# lab4.net
KiCad netlist of a schematic drawn in EAGLE
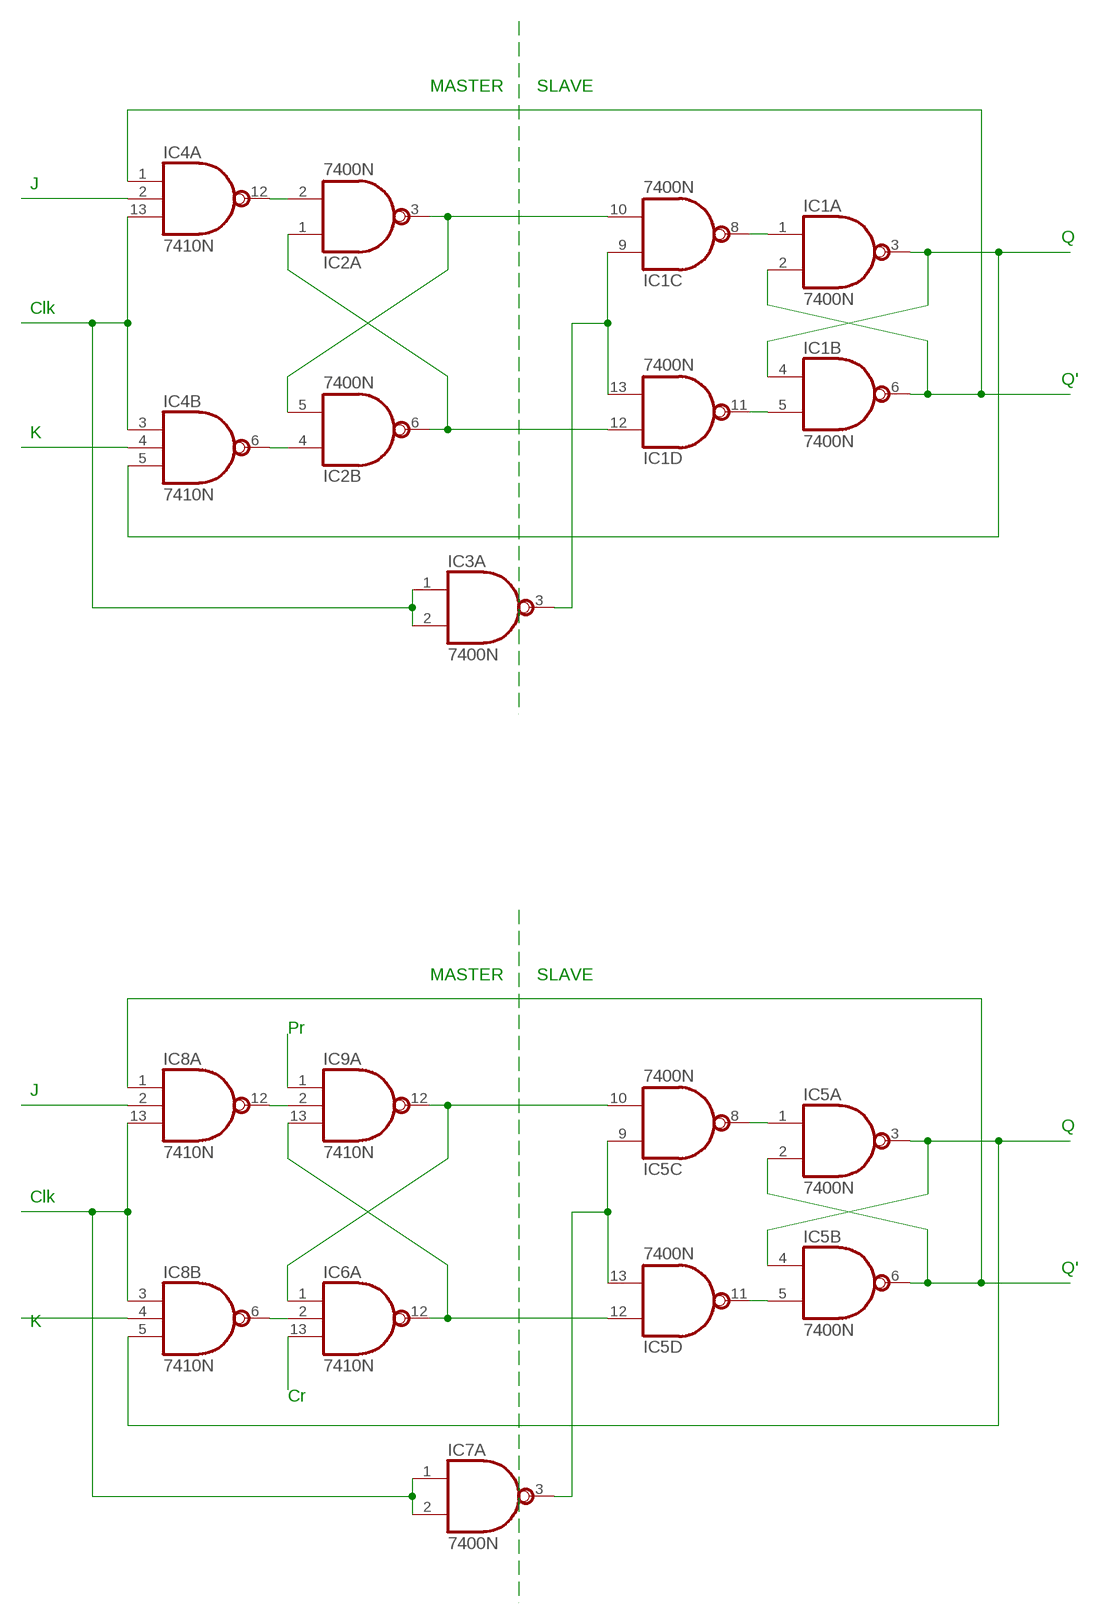
[diagram p0: schematic, sheet 1]

(export (version "E")
  (design (tool "Eeschema 10.0.6"))
  (components
    (comp (ref "IC1")
      (value "7400N")
      (footprint "eagle-import:DIL14")
      (libsource (lib "eagle-import") (part "7400N"))
    )
    (comp (ref "IC2")
      (value "7400N")
      (footprint "eagle-import:DIL14")
      (libsource (lib "eagle-import") (part "7400N"))
    )
    (comp (ref "IC3")
      (value "7400N")
      (footprint "eagle-import:DIL14")
      (libsource (lib "eagle-import") (part "7400N"))
    )
    (comp (ref "IC4")
      (value "7410N")
      (footprint "eagle-import:DIL14")
      (libsource (lib "eagle-import") (part "7410N"))
    )
    (comp (ref "IC5")
      (value "7400N")
      (footprint "eagle-import:DIL14")
      (libsource (lib "eagle-import") (part "7400N"))
    )
    (comp (ref "IC6")
      (value "7410N")
      (footprint "eagle-import:DIL14")
      (libsource (lib "eagle-import") (part "7410N"))
    )
    (comp (ref "IC7")
      (value "7400N")
      (footprint "eagle-import:DIL14")
      (libsource (lib "eagle-import") (part "7400N"))
    )
    (comp (ref "IC8")
      (value "7410N")
      (footprint "eagle-import:DIL14")
      (libsource (lib "eagle-import") (part "7410N"))
    )
    (comp (ref "IC9")
      (value "7410N")
      (footprint "eagle-import:DIL14")
      (libsource (lib "eagle-import") (part "7410N"))
    )
  )
  (nets
    (net (code "1") (name "Net-(IC1A-I0)") (class "Default")
      (node (ref "IC1") (pin "1") (pinfunction "I0_1") (pintype "input"))
      (node (ref "IC1") (pin "8") (pinfunction "O_8") (pintype "output"))
    )
    (net (code "2") (name "Net-(IC1A-I1)") (class "Default")
      (node (ref "IC1") (pin "2") (pinfunction "I1_2") (pintype "input"))
      (node (ref "IC1") (pin "6") (pinfunction "O_6") (pintype "output"))
      (node (ref "IC4") (pin "1") (pinfunction "I0_1") (pintype "input"))
    )
    (net (code "3") (name "Net-(IC1A-O)") (class "Default")
      (node (ref "IC1") (pin "3") (pinfunction "O_3") (pintype "output"))
      (node (ref "IC1") (pin "4") (pinfunction "I0_4") (pintype "input"))
      (node (ref "IC4") (pin "5") (pinfunction "I2_5") (pintype "input"))
    )
    (net (code "4") (name "Net-(IC1B-I1)") (class "Default")
      (node (ref "IC1") (pin "11") (pinfunction "O_11") (pintype "output"))
      (node (ref "IC1") (pin "5") (pinfunction "I1_5") (pintype "input"))
    )
    (net (code "5") (name "Net-(IC1C-I0)") (class "Default")
      (node (ref "IC1") (pin "13") (pinfunction "I1_13") (pintype "input"))
      (node (ref "IC1") (pin "9") (pinfunction "I0_9") (pintype "input"))
      (node (ref "IC3") (pin "3") (pinfunction "O_3") (pintype "output"))
    )
    (net (code "6") (name "Net-(IC1C-I1)") (class "Default")
      (node (ref "IC1") (pin "10") (pinfunction "I1_10") (pintype "input"))
      (node (ref "IC2") (pin "3") (pinfunction "O_3") (pintype "output"))
      (node (ref "IC2") (pin "5") (pinfunction "I1_5") (pintype "input"))
    )
    (net (code "7") (name "Net-(IC1D-I0)") (class "Default")
      (node (ref "IC1") (pin "12") (pinfunction "I0_12") (pintype "input"))
      (node (ref "IC2") (pin "1") (pinfunction "I0_1") (pintype "input"))
      (node (ref "IC2") (pin "6") (pinfunction "O_6") (pintype "output"))
    )
    (net (code "8") (name "Net-(IC2A-I1)") (class "Default")
      (node (ref "IC2") (pin "2") (pinfunction "I1_2") (pintype "input"))
      (node (ref "IC4") (pin "12") (pinfunction "O_12") (pintype "output"))
    )
    (net (code "9") (name "Net-(IC2B-I0)") (class "Default")
      (node (ref "IC2") (pin "4") (pinfunction "I0_4") (pintype "input"))
      (node (ref "IC4") (pin "6") (pinfunction "O_6") (pintype "output"))
    )
    (net (code "10") (name "Net-(IC3A-I0)") (class "Default")
      (node (ref "IC3") (pin "1") (pinfunction "I0_1") (pintype "input"))
      (node (ref "IC3") (pin "2") (pinfunction "I1_2") (pintype "input"))
      (node (ref "IC4") (pin "13") (pinfunction "I2_13") (pintype "input"))
      (node (ref "IC4") (pin "3") (pinfunction "I0_3") (pintype "input"))
    )
    (net (code "11") (name "Net-(IC5A-I0)") (class "Default")
      (node (ref "IC5") (pin "1") (pinfunction "I0_1") (pintype "input"))
      (node (ref "IC5") (pin "8") (pinfunction "O_8") (pintype "output"))
    )
    (net (code "12") (name "Net-(IC5A-I1)") (class "Default")
      (node (ref "IC5") (pin "2") (pinfunction "I1_2") (pintype "input"))
      (node (ref "IC5") (pin "6") (pinfunction "O_6") (pintype "output"))
      (node (ref "IC8") (pin "1") (pinfunction "I0_1") (pintype "input"))
    )
    (net (code "13") (name "Net-(IC5A-O)") (class "Default")
      (node (ref "IC5") (pin "3") (pinfunction "O_3") (pintype "output"))
      (node (ref "IC5") (pin "4") (pinfunction "I0_4") (pintype "input"))
      (node (ref "IC8") (pin "5") (pinfunction "I2_5") (pintype "input"))
    )
    (net (code "14") (name "Net-(IC5B-I1)") (class "Default")
      (node (ref "IC5") (pin "11") (pinfunction "O_11") (pintype "output"))
      (node (ref "IC5") (pin "5") (pinfunction "I1_5") (pintype "input"))
    )
    (net (code "15") (name "Net-(IC5C-I0)") (class "Default")
      (node (ref "IC5") (pin "13") (pinfunction "I1_13") (pintype "input"))
      (node (ref "IC5") (pin "9") (pinfunction "I0_9") (pintype "input"))
      (node (ref "IC7") (pin "3") (pinfunction "O_3") (pintype "output"))
    )
    (net (code "16") (name "Net-(IC5C-I1)") (class "Default")
      (node (ref "IC5") (pin "10") (pinfunction "I1_10") (pintype "input"))
      (node (ref "IC6") (pin "1") (pinfunction "I0_1") (pintype "input"))
      (node (ref "IC9") (pin "12") (pinfunction "O_12") (pintype "output"))
    )
    (net (code "17") (name "Net-(IC5D-I0)") (class "Default")
      (node (ref "IC5") (pin "12") (pinfunction "I0_12") (pintype "input"))
      (node (ref "IC6") (pin "12") (pinfunction "O_12") (pintype "output"))
      (node (ref "IC9") (pin "13") (pinfunction "I2_13") (pintype "input"))
    )
    (net (code "18") (name "Net-(IC6A-I1)") (class "Default")
      (node (ref "IC6") (pin "2") (pinfunction "I1_2") (pintype "input"))
      (node (ref "IC8") (pin "6") (pinfunction "O_6") (pintype "output"))
    )
    (net (code "19") (name "Net-(IC7A-I0)") (class "Default")
      (node (ref "IC7") (pin "1") (pinfunction "I0_1") (pintype "input"))
      (node (ref "IC7") (pin "2") (pinfunction "I1_2") (pintype "input"))
      (node (ref "IC8") (pin "13") (pinfunction "I2_13") (pintype "input"))
      (node (ref "IC8") (pin "3") (pinfunction "I0_3") (pintype "input"))
    )
    (net (code "20") (name "Net-(IC8A-O)") (class "Default")
      (node (ref "IC8") (pin "12") (pinfunction "O_12") (pintype "output"))
      (node (ref "IC9") (pin "2") (pinfunction "I1_2") (pintype "input"))
    )
    (net (code "21") (name "unconnected-(IC4A-I1-Pad2)") (class "Default")
      (node (ref "IC4") (pin "2") (pinfunction "I1_2") (pintype "input"))
    )
    (net (code "22") (name "unconnected-(IC4B-I1-Pad4)") (class "Default")
      (node (ref "IC4") (pin "4") (pinfunction "I1_4") (pintype "input"))
    )
    (net (code "23") (name "unconnected-(IC6A-I2-Pad13)") (class "Default")
      (node (ref "IC6") (pin "13") (pinfunction "I2_13") (pintype "input"))
    )
    (net (code "24") (name "unconnected-(IC8A-I1-Pad2)") (class "Default")
      (node (ref "IC8") (pin "2") (pinfunction "I1_2") (pintype "input"))
    )
    (net (code "25") (name "unconnected-(IC8B-I1-Pad4)") (class "Default")
      (node (ref "IC8") (pin "4") (pinfunction "I1_4") (pintype "input"))
    )
    (net (code "26") (name "unconnected-(IC9A-I0-Pad1)") (class "Default")
      (node (ref "IC9") (pin "1") (pinfunction "I0_1") (pintype "input"))
    )
  )
)
